# mainboard.net
KiCad netlist of a schematic drawn in EAGLE
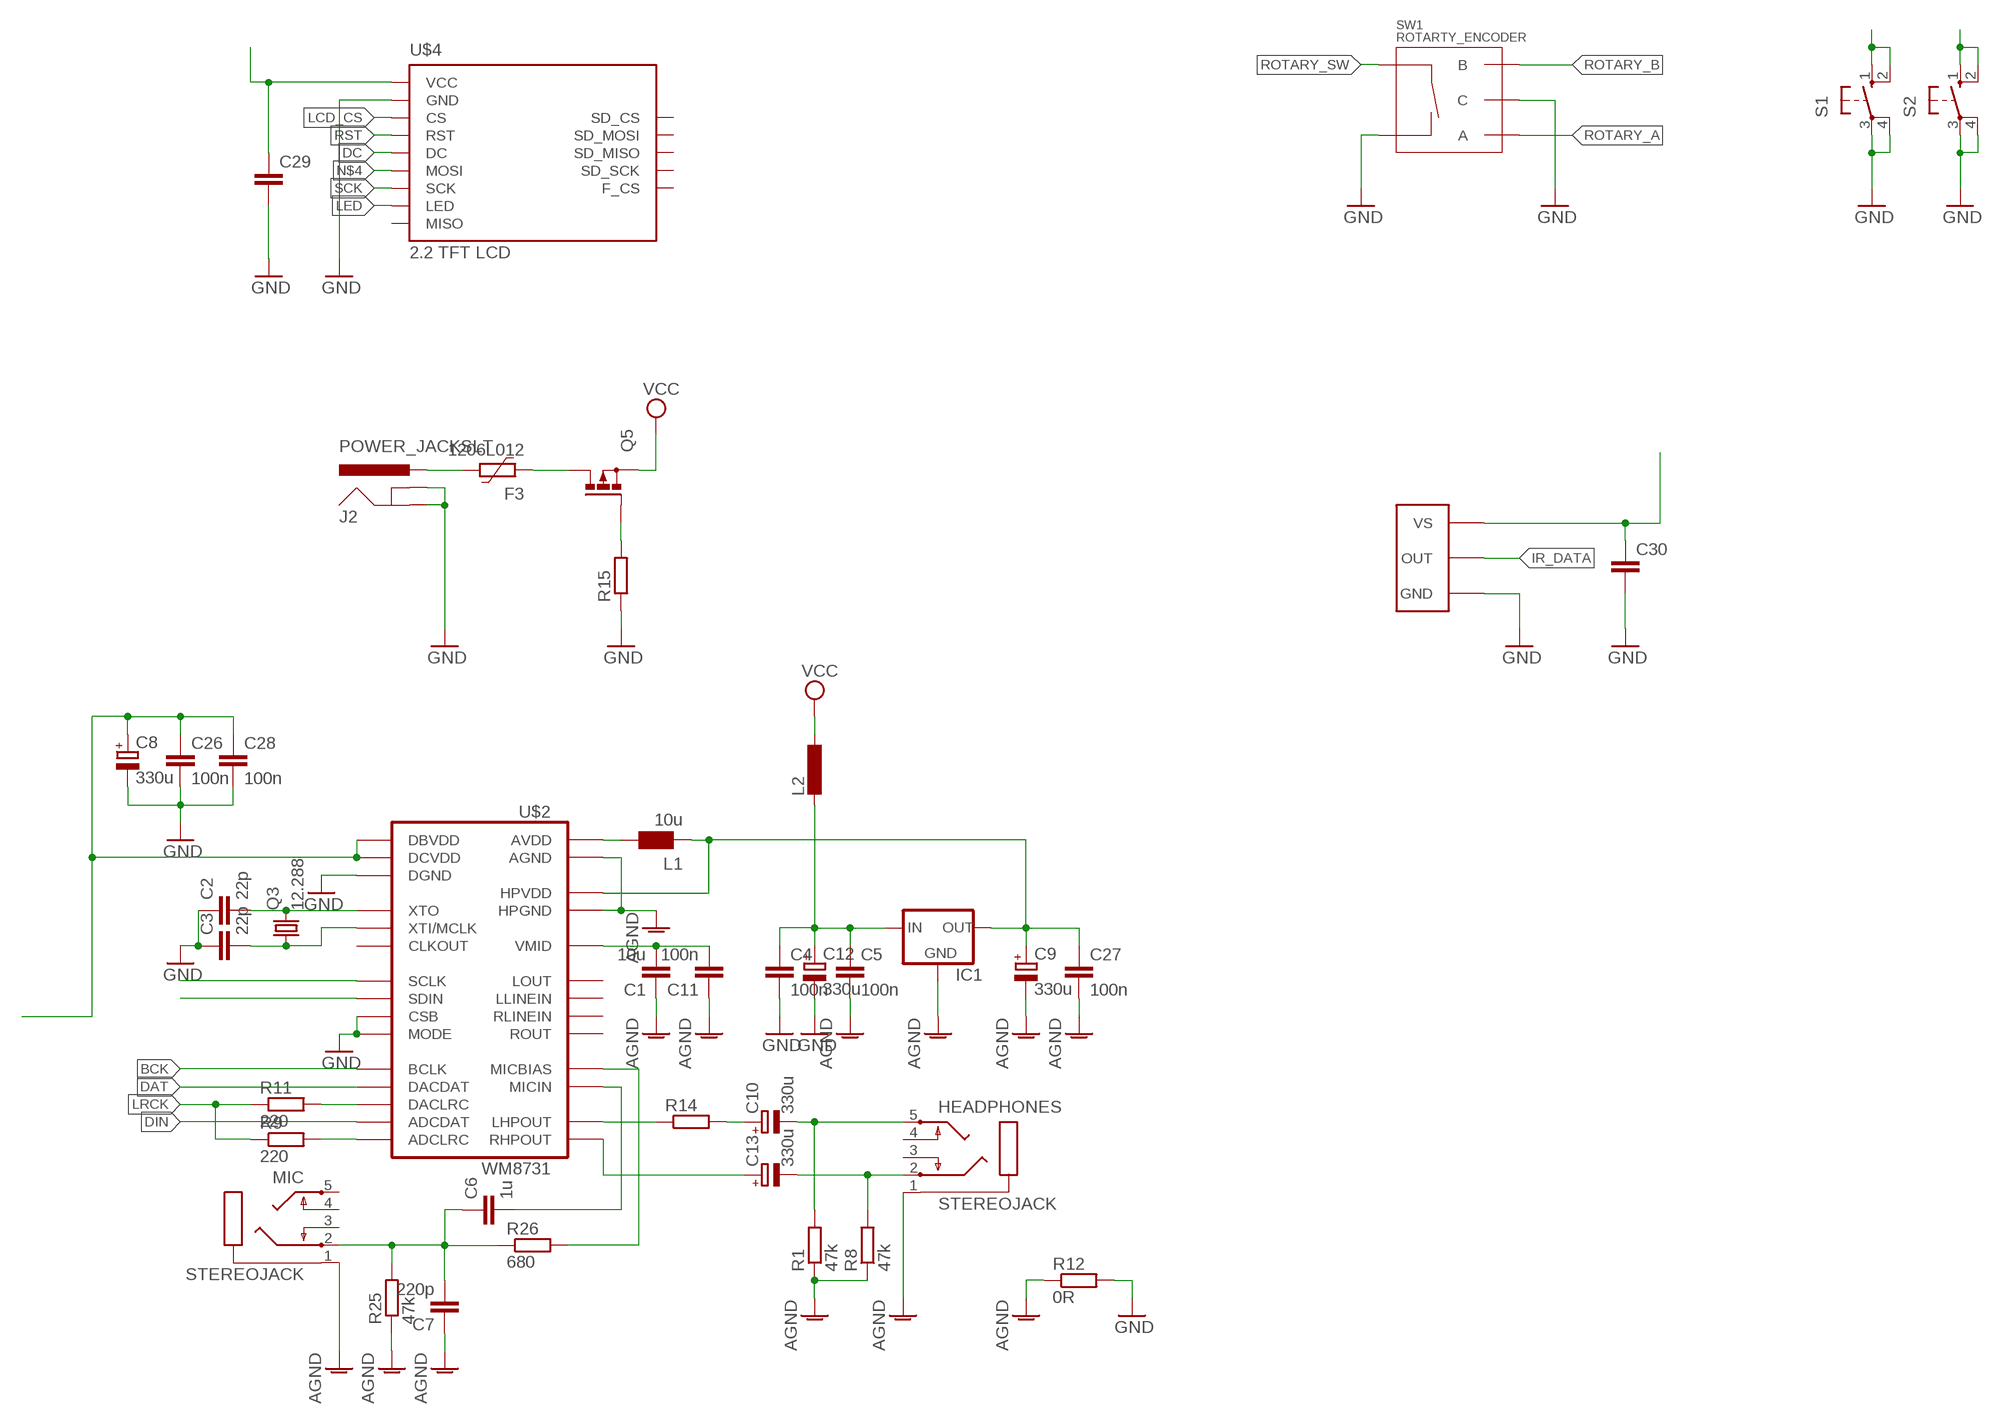
[diagram p0: schematic, sheet 1, part 1 of 2]
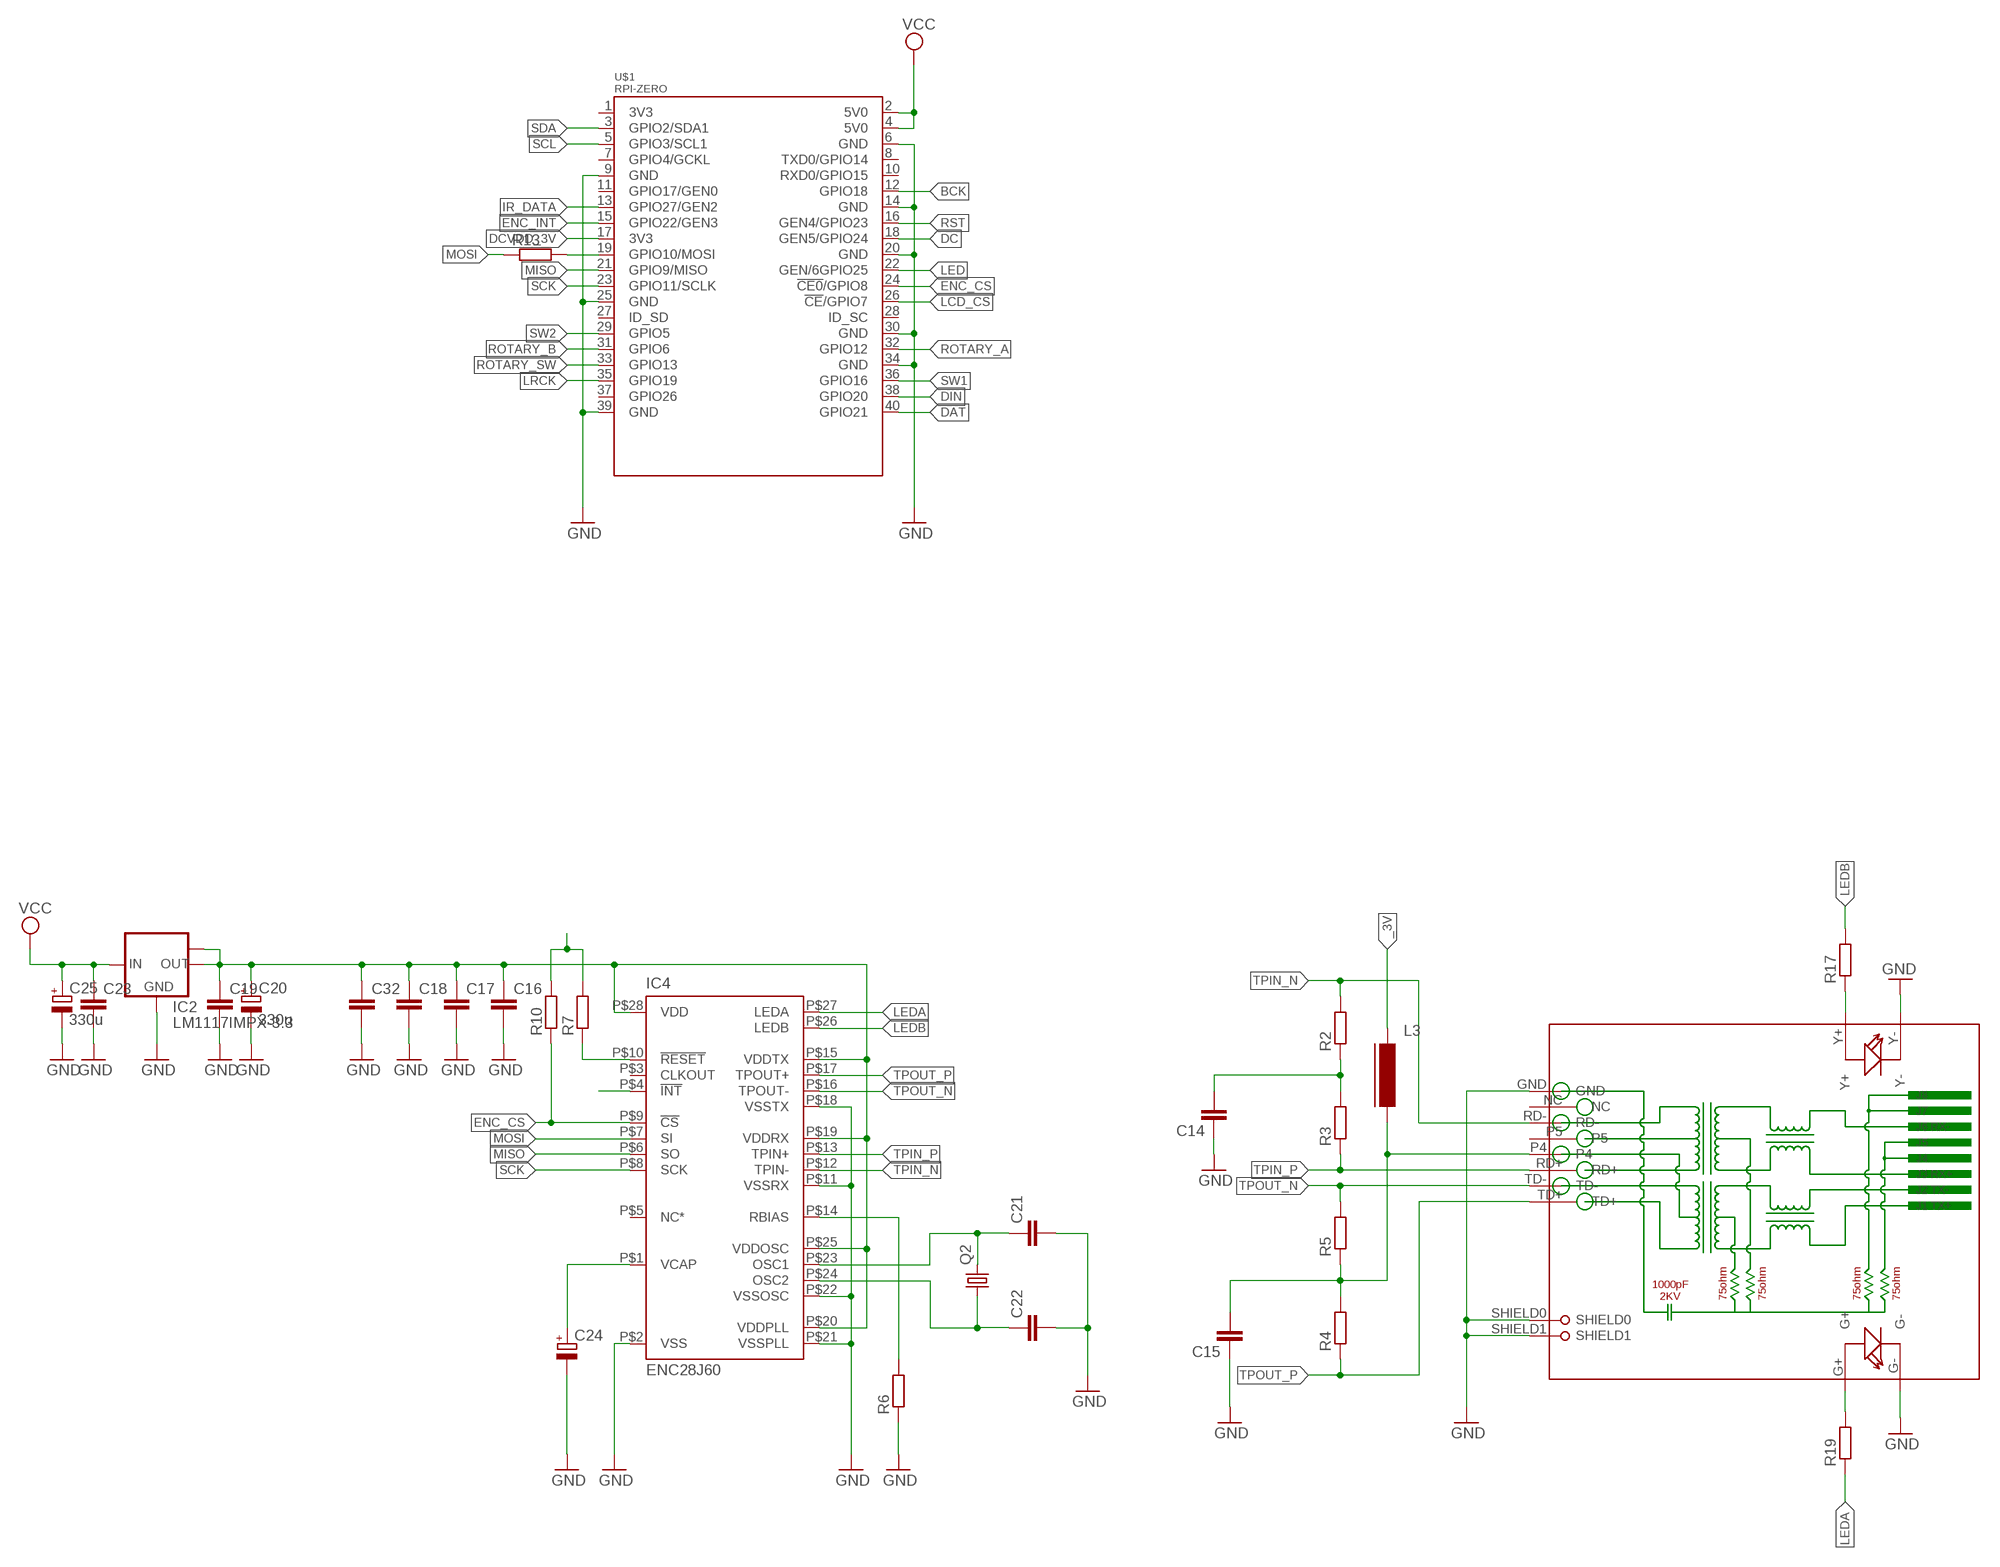
[diagram p1: schematic, sheet 1, part 2 of 2]

(export (version "E")
  (design (tool "Eeschema 10.0.6"))
  (components
    (comp (ref "C1")
      (value "10u")
      (footprint "eagle-import:C0603")
      (libsource (lib "eagle-import") (part "C-EUC0603"))
    )
    (comp (ref "C2")
      (value "22p")
      (footprint "eagle-import:C0603")
      (libsource (lib "eagle-import") (part "C-EUC0603"))
    )
    (comp (ref "C3")
      (value "22p")
      (footprint "eagle-import:C0603")
      (libsource (lib "eagle-import") (part "C-EUC0603"))
    )
    (comp (ref "C4")
      (value "100n")
      (footprint "eagle-import:C0603")
      (libsource (lib "eagle-import") (part "C-EUC0603"))
    )
    (comp (ref "C5")
      (value "100n")
      (footprint "eagle-import:C0603")
      (libsource (lib "eagle-import") (part "C-EUC0603"))
    )
    (comp (ref "C6")
      (value "1u")
      (footprint "eagle-import:C0603")
      (libsource (lib "eagle-import") (part "C-EUC0603"))
    )
    (comp (ref "C7")
      (value "220p")
      (footprint "eagle-import:C0603")
      (libsource (lib "eagle-import") (part "C-EUC0603"))
    )
    (comp (ref "C8")
      (value "330u")
      (footprint "eagle-import:SMC_B")
      (libsource (lib "eagle-import") (part "CPOL-EUSMCB"))
    )
    (comp (ref "C9")
      (value "330u")
      (footprint "eagle-import:SMC_B")
      (libsource (lib "eagle-import") (part "CPOL-EUSMCB"))
    )
    (comp (ref "C10")
      (value "330u")
      (footprint "eagle-import:E3,5-8")
      (libsource (lib "eagle-import") (part "CPOL-EUE3.5-8"))
    )
    (comp (ref "C11")
      (value "100n")
      (footprint "eagle-import:C0603")
      (libsource (lib "eagle-import") (part "C-EUC0603"))
    )
    (comp (ref "C12")
      (value "330u")
      (footprint "eagle-import:SMC_B")
      (libsource (lib "eagle-import") (part "CPOL-EUSMCB"))
    )
    (comp (ref "C13")
      (value "330u")
      (footprint "eagle-import:E3,5-8")
      (libsource (lib "eagle-import") (part "CPOL-EUE3.5-8"))
    )
    (comp (ref "C14")
      (value "C-EUC0603")
      (footprint "eagle-import:C0603")
      (libsource (lib "eagle-import") (part "C-EUC0603"))
    )
    (comp (ref "C15")
      (value "C-EUC0603")
      (footprint "eagle-import:C0603")
      (libsource (lib "eagle-import") (part "C-EUC0603"))
    )
    (comp (ref "C16")
      (value "C-EUC0402")
      (footprint "eagle-import:C0402")
      (libsource (lib "eagle-import") (part "C-EUC0402"))
    )
    (comp (ref "C17")
      (value "C-EUC0402")
      (footprint "eagle-import:C0402")
      (libsource (lib "eagle-import") (part "C-EUC0402"))
    )
    (comp (ref "C18")
      (value "C-EUC0402")
      (footprint "eagle-import:C0402")
      (libsource (lib "eagle-import") (part "C-EUC0402"))
    )
    (comp (ref "C19")
      (value "C-EUC0603")
      (footprint "eagle-import:C0603")
      (libsource (lib "eagle-import") (part "C-EUC0603"))
    )
    (comp (ref "C20")
      (value "330u")
      (footprint "eagle-import:SMC_B")
      (libsource (lib "eagle-import") (part "CPOL-EUSMCB"))
    )
    (comp (ref "C21")
      (value "C-EUC0603")
      (footprint "eagle-import:C0603")
      (libsource (lib "eagle-import") (part "C-EUC0603"))
    )
    (comp (ref "C22")
      (value "C-EUC0603")
      (footprint "eagle-import:C0603")
      (libsource (lib "eagle-import") (part "C-EUC0603"))
    )
    (comp (ref "C23")
      (value "C-EUC0603")
      (footprint "eagle-import:C0603")
      (libsource (lib "eagle-import") (part "C-EUC0603"))
    )
    (comp (ref "C24")
      (value "CPOL-EUSMCA")
      (footprint "eagle-import:SMC_A")
      (libsource (lib "eagle-import") (part "CPOL-EUSMCA"))
    )
    (comp (ref "C25")
      (value "330u")
      (footprint "eagle-import:SMC_B")
      (libsource (lib "eagle-import") (part "CPOL-EUSMCB"))
    )
    (comp (ref "C26")
      (value "100n")
      (footprint "eagle-import:C0603")
      (libsource (lib "eagle-import") (part "C-EUC0603"))
    )
    (comp (ref "C27")
      (value "100n")
      (footprint "eagle-import:C0603")
      (libsource (lib "eagle-import") (part "C-EUC0603"))
    )
    (comp (ref "C28")
      (value "100n")
      (footprint "eagle-import:C0603")
      (libsource (lib "eagle-import") (part "C-EUC0603"))
    )
    (comp (ref "C29")
      (value "C-EUC0603")
      (footprint "eagle-import:C0603")
      (libsource (lib "eagle-import") (part "C-EUC0603"))
    )
    (comp (ref "C30")
      (value "C-EUC0603")
      (footprint "eagle-import:C0603")
      (libsource (lib "eagle-import") (part "C-EUC0603"))
    )
    (comp (ref "C32")
      (value "C-EUC0402")
      (footprint "eagle-import:C0402")
      (libsource (lib "eagle-import") (part "C-EUC0402"))
    )
    (comp (ref "F3")
      (value "1206L012")
      (footprint "eagle-import:1206L")
      (fields (field (name "MF") "Littelfuse"))
      (libsource (lib "eagle-import") (part "?1206L012"))
    )
    (comp (ref "HEADPHONES")
      (value "STEREOJACK")
      (footprint "eagle-import:STX3100")
      (libsource (lib "eagle-import") (part "STEREOJACK"))
    )
    (comp (ref "IC1")
      (value "78LXXREV")
      (footprint "eagle-import:78LXX_REV")
      (libsource (lib "eagle-import") (part "78LXXREV"))
    )
    (comp (ref "IC2")
      (value "LM1117IMPX-3.3")
      (footprint "eagle-import:SOT223")
      (libsource (lib "eagle-import") (part "LM1117IMPX-3.3"))
    )
    (comp (ref "IC4")
      (value "ENC28J60")
      (footprint "eagle-import:TSSOP28W")
      (libsource (lib "eagle-import") (part "ENC28J60"))
    )
    (comp (ref "J2")
      (value "POWER_JACKSLT")
      (footprint "eagle-import:POWER_JACK_SLOT")
      (libsource (lib "eagle-import") (part "POWER_JACKSLT"))
    )
    (comp (ref "L1")
      (value "10u")
      (footprint "eagle-import:WE-KI_0805_B")
      (libsource (lib "eagle-import") (part "WE-KI_0805_B"))
    )
    (comp (ref "L2")
      (value "L-EU0204/7")
      (footprint "eagle-import:0204_7")
      (libsource (lib "eagle-import") (part "L-EU0204/7"))
    )
    (comp (ref "L3")
      (value "FERRITE-0805")
      (footprint "eagle-import:FB805")
      (libsource (lib "eagle-import") (part "FERRITE-0805"))
    )
    (comp (ref "MIC")
      (value "STEREOJACK")
      (footprint "eagle-import:STX3100")
      (libsource (lib "eagle-import") (part "STEREOJACK"))
    )
    (comp (ref "Q2")
      (value "CRYSTALHC49S")
      (footprint "eagle-import:HC49_S")
      (libsource (lib "eagle-import") (part "CRYSTALHC49S"))
    )
    (comp (ref "Q3")
      (value "12.288")
      (footprint "eagle-import:HC49U70")
      (libsource (lib "eagle-import") (part "CRYSTALHC49U70"))
    )
    (comp (ref "Q5")
      (value "P-MOSFET-SO8")
      (footprint "eagle-import:SO-08")
      (libsource (lib "eagle-import") (part "P-MOSFET-SO8"))
    )
    (comp (ref "R1")
      (value "47k")
      (footprint "eagle-import:R0603")
      (libsource (lib "eagle-import") (part "R-EU_R0603"))
    )
    (comp (ref "R2")
      (value "R-EU_R0603")
      (footprint "eagle-import:R0603")
      (libsource (lib "eagle-import") (part "R-EU_R0603"))
    )
    (comp (ref "R3")
      (value "R-EU_R0603")
      (footprint "eagle-import:R0603")
      (libsource (lib "eagle-import") (part "R-EU_R0603"))
    )
    (comp (ref "R4")
      (value "R-EU_R0603")
      (footprint "eagle-import:R0603")
      (libsource (lib "eagle-import") (part "R-EU_R0603"))
    )
    (comp (ref "R5")
      (value "R-EU_R0603")
      (footprint "eagle-import:R0603")
      (libsource (lib "eagle-import") (part "R-EU_R0603"))
    )
    (comp (ref "R6")
      (value "R-EU_0204/7")
      (footprint "eagle-import:0204_7")
      (libsource (lib "eagle-import") (part "R-EU_0204/7"))
    )
    (comp (ref "R7")
      (value "R-EU_0204/7")
      (footprint "eagle-import:0204_7")
      (libsource (lib "eagle-import") (part "R-EU_0204/7"))
    )
    (comp (ref "R8")
      (value "47k")
      (footprint "eagle-import:R0603")
      (libsource (lib "eagle-import") (part "R-EU_R0603"))
    )
    (comp (ref "R9")
      (value "220")
      (footprint "eagle-import:R0402")
      (libsource (lib "eagle-import") (part "R-EU_R0402"))
    )
    (comp (ref "R10")
      (value "R-EU_0204/5")
      (footprint "eagle-import:0204_5")
      (libsource (lib "eagle-import") (part "R-EU_0204/5"))
    )
    (comp (ref "R11")
      (value "220")
      (footprint "eagle-import:R0603")
      (libsource (lib "eagle-import") (part "R-EU_R0603"))
    )
    (comp (ref "R12")
      (value "0R")
      (footprint "eagle-import:R0805")
      (libsource (lib "eagle-import") (part "R-EU_R0805"))
    )
    (comp (ref "R13")
      (value "R-EU_R0603")
      (footprint "eagle-import:R0603")
      (libsource (lib "eagle-import") (part "R-EU_R0603"))
    )
    (comp (ref "R14")
      (value "R-EU_R1206")
      (footprint "eagle-import:R1206")
      (libsource (lib "eagle-import") (part "R-EU_R1206"))
    )
    (comp (ref "R15")
      (value "R-EU_R0603")
      (footprint "eagle-import:R0603")
      (libsource (lib "eagle-import") (part "R-EU_R0603"))
    )
    (comp (ref "R17")
      (value "R-EU_R0603")
      (footprint "eagle-import:R0603")
      (libsource (lib "eagle-import") (part "R-EU_R0603"))
    )
    (comp (ref "R19")
      (value "R-EU_R0603")
      (footprint "eagle-import:R0603")
      (libsource (lib "eagle-import") (part "R-EU_R0603"))
    )
    (comp (ref "R25")
      (value "47k")
      (footprint "eagle-import:R0603")
      (libsource (lib "eagle-import") (part "R-EU_R0603"))
    )
    (comp (ref "R26")
      (value "680")
      (footprint "eagle-import:R0603")
      (libsource (lib "eagle-import") (part "R-EU_R0603"))
    )
    (comp (ref "RJ1")
      (value "HR911105A")
      (footprint "eagle-import:HR911105A")
      (libsource (lib "eagle-import") (part "HR911105A"))
    )
    (comp (ref "S1")
      (value "40-XX")
      (footprint "eagle-import:B3F-40XX")
      (fields (field (name "MF") "OMRON COMPONENTS USA") (field (name "MPN") "B3F-4000"))
      (libsource (lib "eagle-import") (part "40-XX"))
    )
    (comp (ref "S2")
      (value "40-XX")
      (footprint "eagle-import:B3F-40XX")
      (fields (field (name "MF") "OMRON COMPONENTS USA") (field (name "MPN") "B3F-4000"))
      (libsource (lib "eagle-import") (part "40-XX"))
    )
    (comp (ref "SW1")
      (value "ROTARTY_ENCODER")
      (footprint "eagle-import:ROTARY_ENC_PLAIN")
      (libsource (lib "eagle-import") (part "ROTARTY_ENCODER"))
    )
    (comp (ref "U$1")
      (value "RPI-ZERO")
      (footprint "eagle-import:RASPBERRYPI_BASTELSTUBE_V13_RASPI_BOARD_B+_FULL")
      (libsource (lib "eagle-import") (part "RPI-ZERO"))
    )
    (comp (ref "U$2")
      (value "WM8731")
      (footprint "eagle-import:28-SSOP")
      (libsource (lib "eagle-import") (part "WM8731"))
    )
    (comp (ref "U$4")
      (value "2.2_TFT_LCD")
      (footprint "eagle-import:2.2_TFT_LCD")
      (libsource (lib "eagle-import") (part "2.2_TFT_LCD"))
    )
    (comp (ref "U$5")
      (value "TSOP312XVERTICAL")
      (footprint "eagle-import:TSOP312X_VERT")
      (libsource (lib "eagle-import") (part "TSOP312XVERTICAL"))
    )
  )
  (nets
    (net (code "1") (name "/3V3") (class "Default")
      (node (ref "U$1") (pin "1") (pinfunction "3V3_1") (pintype "power_in"))
    )
    (net (code "2") (name "AGND") (class "Default")
      (node (ref "C1") (pin "1") (pinfunction "1_1") (pintype "passive"))
      (node (ref "C11") (pin "1") (pinfunction "1_1") (pintype "passive"))
      (node (ref "C27") (pin "2") (pinfunction "2_2") (pintype "passive"))
      (node (ref "C5") (pin "2") (pinfunction "2_2") (pintype "passive"))
      (node (ref "C7") (pin "1") (pinfunction "1_1") (pintype "passive"))
      (node (ref "C9") (pin "-") (pinfunction "-_-") (pintype "passive"))
      (node (ref "HEADPHONES") (pin "1") (pinfunction "1_1") (pintype "passive"))
      (node (ref "IC1") (pin "GND") (pinfunction "GND_GND") (pintype "input"))
      (node (ref "MIC") (pin "1") (pinfunction "1_1") (pintype "passive"))
      (node (ref "R1") (pin "1") (pinfunction "1_1") (pintype "passive"))
      (node (ref "R12") (pin "1") (pinfunction "1_1") (pintype "passive"))
      (node (ref "R25") (pin "1") (pinfunction "1_1") (pintype "passive"))
      (node (ref "R8") (pin "1") (pinfunction "1_1") (pintype "passive"))
      (node (ref "U$2") (pin "P$11") (pinfunction "HPGND_P$11") (pintype "power_in"))
      (node (ref "U$2") (pin "P$15") (pinfunction "AGND_P$15") (pintype "power_in"))
    )
    (net (code "3") (name "BCK") (class "Default")
      (node (ref "U$1") (pin "12") (pinfunction "GPIO18_12") (pintype "bidirectional"))
      (node (ref "U$2") (pin "P$3") (pinfunction "BCLK_P$3") (pintype "bidirectional"))
    )
    (net (code "4") (name "DAT") (class "Default")
      (node (ref "U$1") (pin "40") (pinfunction "GPIO21_40") (pintype "bidirectional"))
      (node (ref "U$2") (pin "P$4") (pinfunction "DACDAT_P$4") (pintype "input"))
    )
    (net (code "5") (name "DC") (class "Default")
      (node (ref "U$1") (pin "18") (pinfunction "GEN5/GPIO24_18") (pintype "bidirectional"))
      (node (ref "U$4") (pin "DC") (pinfunction "DC_DC") (pintype "bidirectional"))
    )
    (net (code "6") (name "DCVDD_3V") (class "Default")
      (node (ref "C26") (pin "1") (pinfunction "1_1") (pintype "passive"))
      (node (ref "C28") (pin "1") (pinfunction "1_1") (pintype "passive"))
      (node (ref "C8") (pin "+") (pinfunction "+_+") (pintype "passive"))
      (node (ref "R10") (pin "2") (pinfunction "2_2") (pintype "passive"))
      (node (ref "R7") (pin "2") (pinfunction "2_2") (pintype "passive"))
      (node (ref "U$1") (pin "17") (pinfunction "3V3_17") (pintype "power_in"))
      (node (ref "U$2") (pin "P$1") (pinfunction "DBVDD_P$1") (pintype "power_in"))
      (node (ref "U$2") (pin "P$27") (pinfunction "DCVDD_P$27") (pintype "power_in"))
    )
    (net (code "7") (name "DIN") (class "Default")
      (node (ref "U$1") (pin "38") (pinfunction "GPIO20_38") (pintype "bidirectional"))
      (node (ref "U$2") (pin "P$6") (pinfunction "ADCDAT_P$6") (pintype "output"))
    )
    (net (code "8") (name "ENC_CS") (class "Default")
      (node (ref "IC4") (pin "P$9") (pinfunction "~{CS}_P$9") (pintype "input"))
      (node (ref "R10") (pin "1") (pinfunction "1_1") (pintype "passive"))
      (node (ref "U$1") (pin "24") (pinfunction "~{CE0}/GPIO8_24") (pintype "bidirectional"))
    )
    (net (code "9") (name "ENC_INT") (class "Default")
      (node (ref "IC4") (pin "P$4") (pinfunction "~{INT}_P$4") (pintype "output"))
      (node (ref "U$1") (pin "15") (pinfunction "GPIO22/GEN3_15") (pintype "bidirectional"))
    )
    (net (code "10") (name "GND") (class "Default")
      (node (ref "C12") (pin "-") (pinfunction "-_-") (pintype "passive"))
      (node (ref "C14") (pin "1") (pinfunction "1_1") (pintype "passive"))
      (node (ref "C15") (pin "1") (pinfunction "1_1") (pintype "passive"))
      (node (ref "C16") (pin "2") (pinfunction "2_2") (pintype "passive"))
      (node (ref "C17") (pin "2") (pinfunction "2_2") (pintype "passive"))
      (node (ref "C18") (pin "2") (pinfunction "2_2") (pintype "passive"))
      (node (ref "C19") (pin "2") (pinfunction "2_2") (pintype "passive"))
      (node (ref "C2") (pin "1") (pinfunction "1_1") (pintype "passive"))
      (node (ref "C20") (pin "-") (pinfunction "-_-") (pintype "passive"))
      (node (ref "C21") (pin "2") (pinfunction "2_2") (pintype "passive"))
      (node (ref "C22") (pin "2") (pinfunction "2_2") (pintype "passive"))
      (node (ref "C23") (pin "2") (pinfunction "2_2") (pintype "passive"))
      (node (ref "C24") (pin "-") (pinfunction "-_-") (pintype "passive"))
      (node (ref "C25") (pin "-") (pinfunction "-_-") (pintype "passive"))
      (node (ref "C26") (pin "2") (pinfunction "2_2") (pintype "passive"))
      (node (ref "C28") (pin "2") (pinfunction "2_2") (pintype "passive"))
      (node (ref "C29") (pin "2") (pinfunction "2_2") (pintype "passive"))
      (node (ref "C3") (pin "1") (pinfunction "1_1") (pintype "passive"))
      (node (ref "C30") (pin "2") (pinfunction "2_2") (pintype "passive"))
      (node (ref "C32") (pin "2") (pinfunction "2_2") (pintype "passive"))
      (node (ref "C4") (pin "2") (pinfunction "2_2") (pintype "passive"))
      (node (ref "C8") (pin "-") (pinfunction "-_-") (pintype "passive"))
      (node (ref "IC2") (pin "1") (pinfunction "GND_1") (pintype "input"))
      (node (ref "IC4") (pin "P$11") (pinfunction "VSSRX_P$11") (pintype "input"))
      (node (ref "IC4") (pin "P$18") (pinfunction "VSSTX_P$18") (pintype "input"))
      (node (ref "IC4") (pin "P$2") (pinfunction "VSS_P$2") (pintype "input"))
      (node (ref "IC4") (pin "P$21") (pinfunction "VSSPLL_P$21") (pintype "input"))
      (node (ref "IC4") (pin "P$22") (pinfunction "VSSOSC_P$22") (pintype "input"))
      (node (ref "J2") (pin "GND@1") (pinfunction "GNDBREAK_GND@1") (pintype "bidirectional"))
      (node (ref "J2") (pin "GND@2") (pinfunction "GND_GND@2") (pintype "bidirectional"))
      (node (ref "R12") (pin "2") (pinfunction "2_2") (pintype "passive"))
      (node (ref "R15") (pin "1") (pinfunction "1_1") (pintype "passive"))
      (node (ref "R6") (pin "1") (pinfunction "1_1") (pintype "passive"))
      (node (ref "RJ1") (pin "G-") (pinfunction "G-_G-") (pintype "bidirectional"))
      (node (ref "RJ1") (pin "GND") (pinfunction "GND_GND") (pintype "bidirectional"))
      (node (ref "RJ1") (pin "SHIELD0") (pinfunction "SHIELD0_SHIELD0") (pintype "bidirectional"))
      (node (ref "RJ1") (pin "SHIELD1") (pinfunction "SHIELD1_SHIELD1") (pintype "bidirectional"))
      (node (ref "RJ1") (pin "Y-") (pinfunction "Y-_Y-") (pintype "bidirectional"))
      (node (ref "S1") (pin "3") (pinfunction "P_3") (pintype "passive"))
      (node (ref "S1") (pin "4") (pinfunction "P1_4") (pintype "passive"))
      (node (ref "S2") (pin "3") (pinfunction "P_3") (pintype "passive"))
      (node (ref "S2") (pin "4") (pinfunction "P1_4") (pintype "passive"))
      (node (ref "SW1") (pin "C") (pinfunction "C_C") (pintype "bidirectional"))
      (node (ref "SW1") (pin "SW-") (pinfunction "SW-_SW-") (pintype "bidirectional"))
      (node (ref "U$1") (pin "14") (pinfunction "GND_14") (pintype "power_in"))
      (node (ref "U$1") (pin "20") (pinfunction "GND_20") (pintype "power_in"))
      (node (ref "U$1") (pin "25") (pinfunction "GND_25") (pintype "power_in"))
      (node (ref "U$1") (pin "30") (pinfunction "GND_30") (pintype "power_in"))
      (node (ref "U$1") (pin "34") (pinfunction "GND_34") (pintype "power_in"))
      (node (ref "U$1") (pin "39") (pinfunction "GND_39") (pintype "power_in"))
      (node (ref "U$1") (pin "6") (pinfunction "GND_6") (pintype "power_in"))
      (node (ref "U$1") (pin "9") (pinfunction "GND_9") (pintype "power_in"))
      (node (ref "U$2") (pin "P$21") (pinfunction "MODE_P$21") (pintype "input"))
      (node (ref "U$2") (pin "P$22") (pinfunction "CSB_P$22") (pintype "input"))
      (node (ref "U$2") (pin "P$28") (pinfunction "DGND_P$28") (pintype "power_in"))
      (node (ref "U$4") (pin "GND") (pinfunction "GND_GND") (pintype "power_in"))
      (node (ref "U$5") (pin "1") (pinfunction "GND_1") (pintype "bidirectional"))
    )
    (net (code "11") (name "IR_DATA") (class "Default")
      (node (ref "U$1") (pin "13") (pinfunction "GPIO27/GEN2_13") (pintype "bidirectional"))
      (node (ref "U$5") (pin "3") (pinfunction "OUT_3") (pintype "bidirectional"))
    )
    (net (code "12") (name "LCD_CS") (class "Default")
      (node (ref "U$1") (pin "26") (pinfunction "~{CE}/GPIO7_26") (pintype "bidirectional"))
      (node (ref "U$4") (pin "CS") (pinfunction "CS_CS") (pintype "bidirectional"))
    )
    (net (code "13") (name "LED") (class "Default")
      (node (ref "U$1") (pin "22") (pinfunction "GEN/6GPIO25_22") (pintype "bidirectional"))
      (node (ref "U$4") (pin "LED") (pinfunction "LED_LED") (pintype "bidirectional"))
    )
    (net (code "14") (name "LEDA") (class "Default")
      (node (ref "IC4") (pin "P$27") (pinfunction "LEDA_P$27") (pintype "output"))
      (node (ref "R19") (pin "1") (pinfunction "1_1") (pintype "passive"))
    )
    (net (code "15") (name "LEDB") (class "Default")
      (node (ref "IC4") (pin "P$26") (pinfunction "LEDB_P$26") (pintype "output"))
      (node (ref "R17") (pin "2") (pinfunction "2_2") (pintype "passive"))
    )
    (net (code "16") (name "LRCK") (class "Default")
      (node (ref "R11") (pin "1") (pinfunction "1_1") (pintype "passive"))
      (node (ref "R9") (pin "1") (pinfunction "1_1") (pintype "passive"))
      (node (ref "U$1") (pin "35") (pinfunction "GPIO19_35") (pintype "bidirectional"))
    )
    (net (code "17") (name "MISO") (class "Default")
      (node (ref "IC4") (pin "P$6") (pinfunction "SO_P$6") (pintype "output"))
      (node (ref "U$1") (pin "21") (pinfunction "GPIO9/MISO_21") (pintype "bidirectional"))
    )
    (net (code "18") (name "MOSI") (class "Default")
      (node (ref "IC4") (pin "P$7") (pinfunction "SI_P$7") (pintype "input"))
      (node (ref "R13") (pin "1") (pinfunction "1_1") (pintype "passive"))
    )
    (net (code "19") (name "N$4") (class "Default")
      (node (ref "R13") (pin "2") (pinfunction "2_2") (pintype "passive"))
      (node (ref "U$1") (pin "19") (pinfunction "GPIO10/MOSI_19") (pintype "bidirectional"))
      (node (ref "U$4") (pin "MOSI") (pinfunction "MOSI_MOSI") (pintype "bidirectional"))
    )
    (net (code "20") (name "Net-(C6-Pad1)") (class "Default")
      (node (ref "C6") (pin "1") (pinfunction "1_1") (pintype "passive"))
      (node (ref "C7") (pin "2") (pinfunction "2_2") (pintype "passive"))
      (node (ref "MIC") (pin "2") (pinfunction "2_2") (pintype "passive"))
      (node (ref "R25") (pin "2") (pinfunction "2_2") (pintype "passive"))
      (node (ref "R26") (pin "1") (pinfunction "1_1") (pintype "passive"))
    )
    (net (code "21") (name "Net-(C10-Pad+)") (class "Default")
      (node (ref "C10") (pin "+") (pinfunction "+_+") (pintype "passive"))
      (node (ref "R14") (pin "2") (pinfunction "2_2") (pintype "passive"))
    )
    (net (code "22") (name "Net-(C10-Pad-)") (class "Default")
      (node (ref "C10") (pin "-") (pinfunction "-_-") (pintype "passive"))
      (node (ref "HEADPHONES") (pin "5") (pinfunction "5_5") (pintype "passive"))
      (node (ref "R1") (pin "2") (pinfunction "2_2") (pintype "passive"))
    )
    (net (code "23") (name "Net-(C12-Pad+)") (class "Default")
      (node (ref "C12") (pin "+") (pinfunction "+_+") (pintype "passive"))
      (node (ref "C4") (pin "1") (pinfunction "1_1") (pintype "passive"))
      (node (ref "C5") (pin "1") (pinfunction "1_1") (pintype "passive"))
      (node (ref "IC1") (pin "IN") (pinfunction "IN_IN") (pintype "input"))
      (node (ref "L2") (pin "2") (pinfunction "2_2") (pintype "passive"))
    )
    (net (code "24") (name "Net-(C13-Pad-)") (class "Default")
      (node (ref "C13") (pin "-") (pinfunction "-_-") (pintype "passive"))
      (node (ref "HEADPHONES") (pin "2") (pinfunction "2_2") (pintype "passive"))
      (node (ref "R8") (pin "2") (pinfunction "2_2") (pintype "passive"))
    )
    (net (code "25") (name "Net-(C14-Pad2)") (class "Default")
      (node (ref "C14") (pin "2") (pinfunction "2_2") (pintype "passive"))
      (node (ref "R2") (pin "1") (pinfunction "1_1") (pintype "passive"))
      (node (ref "R3") (pin "2") (pinfunction "2_2") (pintype "passive"))
    )
    (net (code "26") (name "Net-(C15-Pad2)") (class "Default")
      (node (ref "C15") (pin "2") (pinfunction "2_2") (pintype "passive"))
      (node (ref "L3") (pin "2") (pinfunction "2_2") (pintype "passive"))
      (node (ref "R4") (pin "2") (pinfunction "2_2") (pintype "passive"))
      (node (ref "R5") (pin "1") (pinfunction "1_1") (pintype "passive"))
      (node (ref "RJ1") (pin "P4") (pinfunction "P4_P4") (pintype "bidirectional"))
    )
    (net (code "27") (name "Net-(F3-Pad1)") (class "Default")
      (node (ref "F3") (pin "1") (pinfunction "1_1") (pintype "passive"))
      (node (ref "J2") (pin "PWR") (pinfunction "PWR_PWR") (pintype "bidirectional"))
    )
    (net (code "28") (name "Net-(F3-Pad2)") (class "Default")
      (node (ref "F3") (pin "2") (pinfunction "2_2") (pintype "passive"))
      (node (ref "Q5") (pin "5") (pinfunction "D_5") (pintype "passive"))
      (node (ref "Q5") (pin "6") (pinfunction "D_6") (pintype "passive"))
      (node (ref "Q5") (pin "7") (pinfunction "D_7") (pintype "passive"))
      (node (ref "Q5") (pin "8") (pinfunction "D_8") (pintype "passive"))
    )
    (net (code "29") (name "Net-(IC4-OSC1)") (class "Default")
      (node (ref "C21") (pin "1") (pinfunction "1_1") (pintype "passive"))
      (node (ref "IC4") (pin "P$23") (pinfunction "OSC1_P$23") (pintype "input"))
      (node (ref "Q2") (pin "2") (pinfunction "2_2") (pintype "passive"))
    )
    (net (code "30") (name "Net-(IC4-OSC2)") (class "Default")
      (node (ref "C22") (pin "1") (pinfunction "1_1") (pintype "passive"))
      (node (ref "IC4") (pin "P$24") (pinfunction "OSC2_P$24") (pintype "output"))
      (node (ref "Q2") (pin "1") (pinfunction "1_1") (pintype "passive"))
    )
    (net (code "31") (name "Net-(IC4-RBIAS)") (class "Default")
      (node (ref "IC4") (pin "P$14") (pinfunction "RBIAS_P$14") (pintype "input"))
      (node (ref "R6") (pin "2") (pinfunction "2_2") (pintype "passive"))
    )
    (net (code "32") (name "Net-(IC4-VCAP)") (class "Default")
      (node (ref "C24") (pin "+") (pinfunction "+_+") (pintype "passive"))
      (node (ref "IC4") (pin "P$1") (pinfunction "VCAP_P$1") (pintype "input"))
    )
    (net (code "33") (name "Net-(IC4-~{RESET})") (class "Default")
      (node (ref "IC4") (pin "P$10") (pinfunction "~{RESET}_P$10") (pintype "input"))
      (node (ref "R7") (pin "1") (pinfunction "1_1") (pintype "passive"))
    )
    (net (code "34") (name "Net-(L1-1)") (class "Default")
      (node (ref "C27") (pin "1") (pinfunction "1_1") (pintype "passive"))
      (node (ref "C9") (pin "+") (pinfunction "+_+") (pintype "passive"))
      (node (ref "IC1") (pin "OUT") (pinfunction "OUT_OUT") (pintype "passive"))
      (node (ref "L1") (pin "2") (pinfunction "1_2") (pintype "passive"))
      (node (ref "U$2") (pin "P$8") (pinfunction "HPVDD_P$8") (pintype "power_in"))
    )
    (net (code "35") (name "Net-(L1-2)") (class "Default")
      (node (ref "L1") (pin "1") (pinfunction "2_1") (pintype "passive"))
      (node (ref "U$2") (pin "P$14") (pinfunction "AVDD_P$14") (pintype "power_in"))
    )
    (net (code "36") (name "Net-(Q5-G)") (class "Default")
      (node (ref "Q5") (pin "4") (pinfunction "G_4") (pintype "passive"))
      (node (ref "R15") (pin "2") (pinfunction "2_2") (pintype "passive"))
    )
    (net (code "37") (name "Net-(R17-Pad1)") (class "Default")
      (node (ref "R17") (pin "1") (pinfunction "1_1") (pintype "passive"))
      (node (ref "RJ1") (pin "Y+") (pinfunction "Y+_Y+") (pintype "bidirectional"))
    )
    (net (code "38") (name "Net-(R19-Pad2)") (class "Default")
      (node (ref "R19") (pin "2") (pinfunction "2_2") (pintype "passive"))
      (node (ref "RJ1") (pin "G+") (pinfunction "G+_G+") (pintype "bidirectional"))
    )
    (net (code "39") (name "Net-(U$2-ADCLRC)") (class "Default")
      (node (ref "R9") (pin "2") (pinfunction "2_2") (pintype "passive"))
      (node (ref "U$2") (pin "P$7") (pinfunction "ADCLRC_P$7") (pintype "bidirectional"))
    )
    (net (code "40") (name "Net-(U$2-DACLRC)") (class "Default")
      (node (ref "R11") (pin "2") (pinfunction "2_2") (pintype "passive"))
      (node (ref "U$2") (pin "P$5") (pinfunction "DACLRC_P$5") (pintype "bidirectional"))
    )
    (net (code "41") (name "Net-(U$2-LHPOUT)") (class "Default")
      (node (ref "R14") (pin "1") (pinfunction "1_1") (pintype "passive"))
      (node (ref "U$2") (pin "P$9") (pinfunction "LHPOUT_P$9") (pintype "output"))
    )
    (net (code "42") (name "Net-(U$2-MICBIAS)") (class "Default")
      (node (ref "R26") (pin "2") (pinfunction "2_2") (pintype "passive"))
      (node (ref "U$2") (pin "P$17") (pinfunction "MICBIAS_P$17") (pintype "output"))
    )
    (net (code "43") (name "Net-(U$2-MICIN)") (class "Default")
      (node (ref "C6") (pin "2") (pinfunction "2_2") (pintype "passive"))
      (node (ref "U$2") (pin "P$18") (pinfunction "MICIN_P$18") (pintype "input"))
    )
    (net (code "44") (name "Net-(U$2-RHPOUT)") (class "Default")
      (node (ref "C13") (pin "+") (pinfunction "+_+") (pintype "passive"))
      (node (ref "U$2") (pin "P$10") (pinfunction "RHPOUT_P$10") (pintype "output"))
    )
    (net (code "45") (name "Net-(U$2-VMID)") (class "Default")
      (node (ref "C1") (pin "2") (pinfunction "2_2") (pintype "passive"))
      (node (ref "C11") (pin "2") (pinfunction "2_2") (pintype "passive"))
      (node (ref "U$2") (pin "P$16") (pinfunction "VMID_P$16") (pintype "output"))
    )
    (net (code "46") (name "Net-(U$2-XTI{slash}MCLK)") (class "Default")
      (node (ref "C3") (pin "2") (pinfunction "2_2") (pintype "passive"))
      (node (ref "Q3") (pin "1") (pinfunction "1_1") (pintype "passive"))
      (node (ref "U$2") (pin "P$25") (pinfunction "XTI/MCLK_P$25") (pintype "input"))
    )
    (net (code "47") (name "Net-(U$2-XTO)") (class "Default")
      (node (ref "C2") (pin "2") (pinfunction "2_2") (pintype "passive"))
      (node (ref "Q3") (pin "2") (pinfunction "2_2") (pintype "passive"))
      (node (ref "U$2") (pin "P$26") (pinfunction "XTO_P$26") (pintype "output"))
    )
    (net (code "48") (name "ROTARY_A") (class "Default")
      (node (ref "SW1") (pin "A") (pinfunction "A_A") (pintype "bidirectional"))
      (node (ref "U$1") (pin "32") (pinfunction "GPIO12_32") (pintype "bidirectional"))
    )
    (net (code "49") (name "ROTARY_B") (class "Default")
      (node (ref "SW1") (pin "B") (pinfunction "B_B") (pintype "bidirectional"))
      (node (ref "U$1") (pin "31") (pinfunction "GPIO6_31") (pintype "bidirectional"))
    )
    (net (code "50") (name "ROTARY_SW") (class "Default")
      (node (ref "SW1") (pin "SW+") (pinfunction "SW+_SW+") (pintype "bidirectional"))
      (node (ref "U$1") (pin "33") (pinfunction "GPIO13_33") (pintype "bidirectional"))
    )
    (net (code "51") (name "RST") (class "Default")
      (node (ref "U$1") (pin "16") (pinfunction "GEN4/GPIO23_16") (pintype "bidirectional"))
      (node (ref "U$4") (pin "RST") (pinfunction "RST_RST") (pintype "bidirectional"))
    )
    (net (code "52") (name "SCK") (class "Default")
      (node (ref "IC4") (pin "P$8") (pinfunction "SCK_P$8") (pintype "input"))
      (node (ref "U$1") (pin "23") (pinfunction "GPIO11/SCLK_23") (pintype "bidirectional"))
      (node (ref "U$4") (pin "SCK") (pinfunction "SCK_SCK") (pintype "bidirectional"))
    )
    (net (code "53") (name "SCL") (class "Default")
      (node (ref "U$1") (pin "5") (pinfunction "GPIO3/SCL1_5") (pintype "bidirectional"))
      (node (ref "U$2") (pin "P$24") (pinfunction "SCLK_P$24") (pintype "input"))
    )
    (net (code "54") (name "SDA") (class "Default")
      (node (ref "U$1") (pin "3") (pinfunction "GPIO2/SDA1_3") (pintype "bidirectional"))
      (node (ref "U$2") (pin "P$23") (pinfunction "SDIN_P$23") (pintype "bidirectional"))
    )
    (net (code "55") (name "SW1") (class "Default")
      (node (ref "S1") (pin "1") (pinfunction "S_1") (pintype "passive"))
      (node (ref "S1") (pin "2") (pinfunction "S1_2") (pintype "passive"))
      (node (ref "U$1") (pin "36") (pinfunction "GPIO16_36") (pintype "bidirectional"))
    )
    (net (code "56") (name "SW2") (class "Default")
      (node (ref "S2") (pin "1") (pinfunction "S_1") (pintype "passive"))
      (node (ref "S2") (pin "2") (pinfunction "S1_2") (pintype "passive"))
      (node (ref "U$1") (pin "29") (pinfunction "GPIO5_29") (pintype "bidirectional"))
    )
    (net (code "57") (name "TPIN_N") (class "Default")
      (node (ref "IC4") (pin "P$12") (pinfunction "TPIN-_P$12") (pintype "input"))
      (node (ref "R2") (pin "2") (pinfunction "2_2") (pintype "passive"))
      (node (ref "RJ1") (pin "RD-") (pinfunction "RD-_RD-") (pintype "bidirectional"))
    )
    (net (code "58") (name "TPIN_P") (class "Default")
      (node (ref "IC4") (pin "P$13") (pinfunction "TPIN+_P$13") (pintype "input"))
      (node (ref "R3") (pin "1") (pinfunction "1_1") (pintype "passive"))
      (node (ref "RJ1") (pin "RD+") (pinfunction "RD+_RD+") (pintype "bidirectional"))
    )
    (net (code "59") (name "TPOUT_N") (class "Default")
      (node (ref "IC4") (pin "P$16") (pinfunction "TPOUT-_P$16") (pintype "output"))
      (node (ref "R5") (pin "2") (pinfunction "2_2") (pintype "passive"))
      (node (ref "RJ1") (pin "TD-") (pinfunction "TD-_TD-") (pintype "bidirectional"))
    )
    (net (code "60") (name "TPOUT_P") (class "Default")
      (node (ref "IC4") (pin "P$17") (pinfunction "TPOUT+_P$17") (pintype "output"))
      (node (ref "R4") (pin "1") (pinfunction "1_1") (pintype "passive"))
      (node (ref "RJ1") (pin "TD+") (pinfunction "TD+_TD+") (pintype "bidirectional"))
    )
    (net (code "61") (name "VCC") (class "Default")
      (node (ref "C23") (pin "1") (pinfunction "1_1") (pintype "passive"))
      (node (ref "C25") (pin "+") (pinfunction "+_+") (pintype "passive"))
      (node (ref "IC2") (pin "3") (pinfunction "IN_3") (pintype "input"))
      (node (ref "L2") (pin "1") (pinfunction "1_1") (pintype "passive"))
      (node (ref "Q5") (pin "1") (pinfunction "S_1") (pintype "passive"))
      (node (ref "Q5") (pin "2") (pinfunction "S_2") (pintype "passive"))
      (node (ref "Q5") (pin "3") (pinfunction "S_3") (pintype "passive"))
      (node (ref "U$1") (pin "2") (pinfunction "5V0_2") (pintype "power_in"))
      (node (ref "U$1") (pin "4") (pinfunction "5V0_4") (pintype "power_in"))
    )
    (net (code "62") (name "_3V") (class "Default")
      (node (ref "C16") (pin "1") (pinfunction "1_1") (pintype "passive"))
      (node (ref "C17") (pin "1") (pinfunction "1_1") (pintype "passive"))
      (node (ref "C18") (pin "1") (pinfunction "1_1") (pintype "passive"))
      (node (ref "C19") (pin "1") (pinfunction "1_1") (pintype "passive"))
      (node (ref "C20") (pin "+") (pinfunction "+_+") (pintype "passive"))
      (node (ref "C29") (pin "1") (pinfunction "1_1") (pintype "passive"))
      (node (ref "C30") (pin "1") (pinfunction "1_1") (pintype "passive"))
      (node (ref "C32") (pin "1") (pinfunction "1_1") (pintype "passive"))
      (node (ref "IC2") (pin "2") (pinfunction "OUT_2") (pintype "passive"))
      (node (ref "IC2") (pin "TAB") (pinfunction "OUT1_TAB") (pintype "passive"))
      (node (ref "IC4") (pin "P$15") (pinfunction "VDDTX_P$15") (pintype "input"))
      (node (ref "IC4") (pin "P$19") (pinfunction "VDDRX_P$19") (pintype "input"))
      (node (ref "IC4") (pin "P$20") (pinfunction "VDDPLL_P$20") (pintype "input"))
      (node (ref "IC4") (pin "P$25") (pinfunction "VDDOSC_P$25") (pintype "input"))
      (node (ref "IC4") (pin "P$28") (pinfunction "VDD_P$28") (pintype "input"))
      (node (ref "L3") (pin "1") (pinfunction "1_1") (pintype "passive"))
      (node (ref "U$4") (pin "VCC") (pinfunction "VCC_VCC") (pintype "power_in"))
      (node (ref "U$5") (pin "2") (pinfunction "VS_2") (pintype "bidirectional"))
    )
    (net (code "63") (name "unconnected-(HEADPHONES-Pad3)") (class "Default")
      (node (ref "HEADPHONES") (pin "3") (pinfunction "3_3") (pintype "passive"))
    )
    (net (code "64") (name "unconnected-(HEADPHONES-Pad4)") (class "Default")
      (node (ref "HEADPHONES") (pin "4") (pinfunction "4_4") (pintype "passive"))
    )
    (net (code "65") (name "unconnected-(IC4-CLKOUT-PadP$3)") (class "Default")
      (node (ref "IC4") (pin "P$3") (pinfunction "CLKOUT_P$3") (pintype "output"))
    )
    (net (code "66") (name "unconnected-(IC4-NC*-PadP$5)") (class "Default")
      (node (ref "IC4") (pin "P$5") (pinfunction "NC*_P$5") (pintype "output"))
    )
    (net (code "67") (name "unconnected-(MIC-Pad3)") (class "Default")
      (node (ref "MIC") (pin "3") (pinfunction "3_3") (pintype "passive"))
    )
    (net (code "68") (name "unconnected-(MIC-Pad4)") (class "Default")
      (node (ref "MIC") (pin "4") (pinfunction "4_4") (pintype "passive"))
    )
    (net (code "69") (name "unconnected-(MIC-Pad5)") (class "Default")
      (node (ref "MIC") (pin "5") (pinfunction "5_5") (pintype "passive"))
    )
    (net (code "70") (name "unconnected-(RJ1-PadNC)") (class "Default")
      (node (ref "RJ1") (pin "NC") (pinfunction "NC_NC") (pintype "bidirectional"))
    )
    (net (code "71") (name "unconnected-(RJ1-PadP5)") (class "Default")
      (node (ref "RJ1") (pin "P5") (pinfunction "P5_P5") (pintype "bidirectional"))
    )
    (net (code "72") (name "unconnected-(U$1-GPIO4{slash}GCKL-Pad7)") (class "Default")
      (node (ref "U$1") (pin "7") (pinfunction "GPIO4/GCKL_7") (pintype "bidirectional"))
    )
    (net (code "73") (name "unconnected-(U$1-GPIO17{slash}GEN0-Pad11)") (class "Default")
      (node (ref "U$1") (pin "11") (pinfunction "GPIO17/GEN0_11") (pintype "bidirectional"))
    )
    (net (code "74") (name "unconnected-(U$1-GPIO26-Pad37)") (class "Default")
      (node (ref "U$1") (pin "37") (pinfunction "GPIO26_37") (pintype "bidirectional"))
    )
    (net (code "75") (name "unconnected-(U$1-ID_SC-Pad28)") (class "Default")
      (node (ref "U$1") (pin "28") (pinfunction "ID_SC_28") (pintype "bidirectional"))
    )
    (net (code "76") (name "unconnected-(U$1-ID_SD-Pad27)") (class "Default")
      (node (ref "U$1") (pin "27") (pinfunction "ID_SD_27") (pintype "bidirectional"))
    )
    (net (code "77") (name "unconnected-(U$1-RXD0{slash}GPIO15-Pad10)") (class "Default")
      (node (ref "U$1") (pin "10") (pinfunction "RXD0/GPIO15_10") (pintype "bidirectional"))
    )
    (net (code "78") (name "unconnected-(U$1-TXD0{slash}GPIO14-Pad8)") (class "Default")
      (node (ref "U$1") (pin "8") (pinfunction "TXD0/GPIO14_8") (pintype "bidirectional"))
    )
    (net (code "79") (name "unconnected-(U$2-CLKOUT-PadP$2)") (class "Default")
      (node (ref "U$2") (pin "P$2") (pinfunction "CLKOUT_P$2") (pintype "output"))
    )
    (net (code "80") (name "unconnected-(U$2-LLINEIN-PadP$20)") (class "Default")
      (node (ref "U$2") (pin "P$20") (pinfunction "LLINEIN_P$20") (pintype "input"))
    )
    (net (code "81") (name "unconnected-(U$2-LOUT-PadP$12)") (class "Default")
      (node (ref "U$2") (pin "P$12") (pinfunction "LOUT_P$12") (pintype "output"))
    )
    (net (code "82") (name "unconnected-(U$2-RLINEIN-PadP$19)") (class "Default")
      (node (ref "U$2") (pin "P$19") (pinfunction "RLINEIN_P$19") (pintype "input"))
    )
    (net (code "83") (name "unconnected-(U$2-ROUT-PadP$13)") (class "Default")
      (node (ref "U$2") (pin "P$13") (pinfunction "ROUT_P$13") (pintype "output"))
    )
    (net (code "84") (name "unconnected-(U$4-PadF_CS)") (class "Default")
      (node (ref "U$4") (pin "F_CS") (pinfunction "F_CS_F_CS") (pintype "bidirectional"))
    )
    (net (code "85") (name "unconnected-(U$4-PadMISO)") (class "Default")
      (node (ref "U$4") (pin "MISO") (pinfunction "MISO_MISO") (pintype "bidirectional"))
    )
    (net (code "86") (name "unconnected-(U$4-PadSD_CS)") (class "Default")
      (node (ref "U$4") (pin "SD_CS") (pinfunction "SD_CS_SD_CS") (pintype "bidirectional"))
    )
    (net (code "87") (name "unconnected-(U$4-PadSD_MISO)") (class "Default")
      (node (ref "U$4") (pin "SD_MISO") (pinfunction "SD_MISO_SD_MISO") (pintype "bidirectional"))
    )
    (net (code "88") (name "unconnected-(U$4-PadSD_MOSI)") (class "Default")
      (node (ref "U$4") (pin "SD_MOSI") (pinfunction "SD_MOSI_SD_MOSI") (pintype "bidirectional"))
    )
    (net (code "89") (name "unconnected-(U$4-PadSD_SCK)") (class "Default")
      (node (ref "U$4") (pin "SD_SCK") (pinfunction "SD_SCK_SD_SCK") (pintype "bidirectional"))
    )
  )
)
